# ble_clone.net
KiCad netlist of a schematic drawn in EAGLE
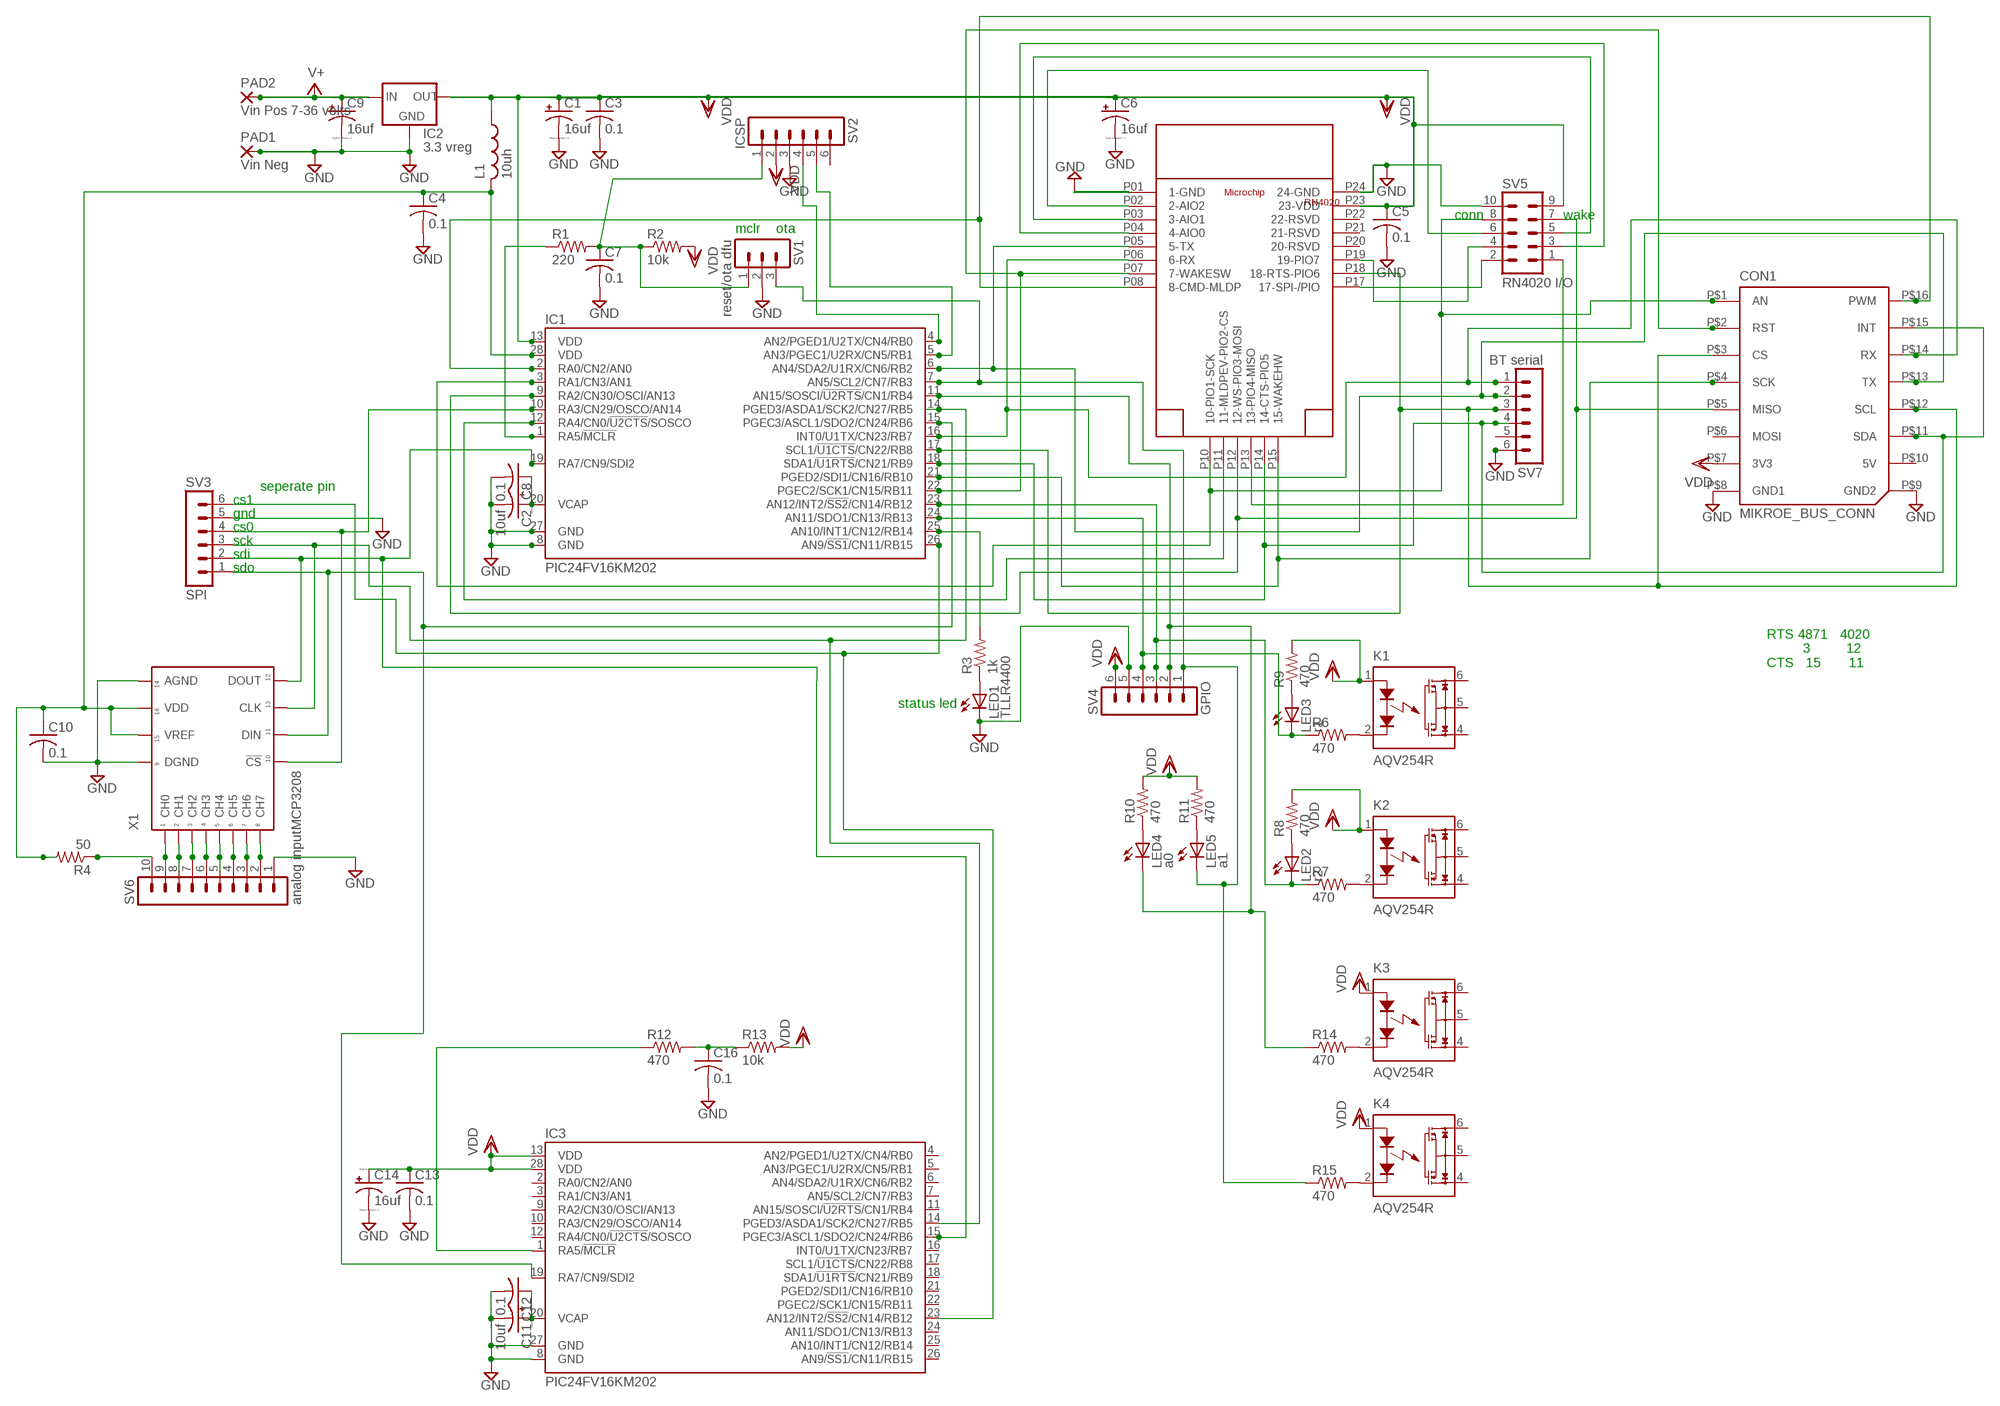
[diagram p0: schematic, sheet 1]

(export (version "E")
  (design (tool "Eeschema 10.0.6"))
  (components
    (comp (ref "C1")
      (value "16uf")
      (footprint "eagle-import:TAP5-45")
      (libsource (lib "eagle-import") (part "CPOL-USTAP5-45"))
    )
    (comp (ref "C2")
      (value "10uf")
      (footprint "eagle-import:TAP5-45")
      (libsource (lib "eagle-import") (part "CPOL-USTAP5-45"))
    )
    (comp (ref "C3")
      (value "0.1")
      (footprint "eagle-import:C025-024X044")
      (libsource (lib "eagle-import") (part "resistor_C-US025-024X044"))
    )
    (comp (ref "C4")
      (value "0.1")
      (footprint "eagle-import:C025-024X044")
      (libsource (lib "eagle-import") (part "resistor_C-US025-024X044"))
    )
    (comp (ref "C5")
      (value "0.1")
      (footprint "eagle-import:C025-024X044")
      (libsource (lib "eagle-import") (part "resistor_C-US025-024X044"))
    )
    (comp (ref "C6")
      (value "16uf")
      (footprint "eagle-import:TAP5-45")
      (libsource (lib "eagle-import") (part "CPOL-USTAP5-45"))
    )
    (comp (ref "C7")
      (value "0.1")
      (footprint "eagle-import:C025-024X044")
      (libsource (lib "eagle-import") (part "resistor_C-US025-024X044"))
    )
    (comp (ref "C8")
      (value "0.1")
      (footprint "eagle-import:C025-024X044")
      (libsource (lib "eagle-import") (part "resistor_C-US025-024X044"))
    )
    (comp (ref "C9")
      (value "16uf")
      (footprint "eagle-import:TAP5-45")
      (libsource (lib "eagle-import") (part "CPOL-USTAP5-45"))
    )
    (comp (ref "C10")
      (value "0.1")
      (footprint "eagle-import:C025-024X044")
      (libsource (lib "eagle-import") (part "resistor_C-US025-024X044"))
    )
    (comp (ref "C11")
      (value "10uf")
      (footprint "eagle-import:TAP5-45")
      (libsource (lib "eagle-import") (part "CPOL-USTAP5-45"))
    )
    (comp (ref "C12")
      (value "0.1")
      (footprint "eagle-import:C0805")
      (libsource (lib "eagle-import") (part "C-USC0805"))
    )
    (comp (ref "C13")
      (value "0.1")
      (footprint "eagle-import:C0805")
      (libsource (lib "eagle-import") (part "C-USC0805"))
    )
    (comp (ref "C14")
      (value "16uf")
      (footprint "eagle-import:TAP5-45")
      (libsource (lib "eagle-import") (part "CPOL-USTAP5-45"))
    )
    (comp (ref "C16")
      (value "0.1")
      (footprint "eagle-import:C0805")
      (libsource (lib "eagle-import") (part "C-USC0805"))
    )
    (comp (ref "CON1")
      (value "MIKROE_BUS_CONN")
      (footprint "eagle-import:MIKROBUS_HOST_CONN")
      (libsource (lib "eagle-import") (part "MIKROE_BUS_CONN"))
    )
    (comp (ref "IC1")
      (value "PIC24FV16KM202")
      (footprint "eagle-import:DIL28-3")
      (libsource (lib "eagle-import") (part "PIC24FVXXKA302-SP"))
    )
    (comp (ref "IC2")
      (value "3.3 vreg")
      (footprint "eagle-import:78XXL")
      (libsource (lib "eagle-import") (part "78XXL"))
    )
    (comp (ref "IC3")
      (value "PIC24FV16KM202")
      (footprint "eagle-import:DIL28-3")
      (libsource (lib "eagle-import") (part "PIC24FVXXKA302-SP"))
    )
    (comp (ref "K1")
      (value "AQV254R")
      (footprint "eagle-import:DIL06")
      (fields (field (name "MF") "AROMAT/ MATSUSHITA") (field (name "MPN") "AQV254"))
      (libsource (lib "eagle-import") (part "AQV254R"))
    )
    (comp (ref "K2")
      (value "AQV254R")
      (footprint "eagle-import:DIL06")
      (fields (field (name "MF") "AROMAT/ MATSUSHITA") (field (name "MPN") "AQV254"))
      (libsource (lib "eagle-import") (part "AQV254R"))
    )
    (comp (ref "K3")
      (value "AQV254R")
      (footprint "eagle-import:DIL06")
      (fields (field (name "MF") "AROMAT/ MATSUSHITA") (field (name "MPN") "AQV254"))
      (libsource (lib "eagle-import") (part "AQV254R"))
    )
    (comp (ref "K4")
      (value "AQV254R")
      (footprint "eagle-import:DIL06")
      (fields (field (name "MF") "AROMAT/ MATSUSHITA") (field (name "MPN") "AQV254"))
      (libsource (lib "eagle-import") (part "AQV254R"))
    )
    (comp (ref "L1")
      (value "10uh")
      (footprint "eagle-import:0204_5")
      (libsource (lib "eagle-import") (part "L-US0204/5"))
    )
    (comp (ref "LED1")
      (value "TLLR4400")
      (footprint "eagle-import:LED3MM")
      (fields (field (name "MF") "VISHAY SEMICONDUCTOR"))
      (libsource (lib "eagle-import") (part "TLLR4400"))
    )
    (comp (ref "LED2")
      (value "r2")
      (footprint "eagle-import:LED3MM")
      (libsource (lib "eagle-import") (part "LED3MM"))
    )
    (comp (ref "LED3")
      (value "r1")
      (footprint "eagle-import:LED3MM")
      (libsource (lib "eagle-import") (part "LED3MM"))
    )
    (comp (ref "LED4")
      (value "a0")
      (footprint "eagle-import:LED3MM")
      (libsource (lib "eagle-import") (part "LED3MM"))
    )
    (comp (ref "LED5")
      (value "a1")
      (footprint "eagle-import:LED3MM")
      (libsource (lib "eagle-import") (part "LED3MM"))
    )
    (comp (ref "PAD1")
      (value "Vin Neg")
      (footprint "eagle-import:2,54_1,0")
      (libsource (lib "eagle-import") (part "2,54/1,0"))
    )
    (comp (ref "PAD2")
      (value "Vin Pos 7-36 volts")
      (footprint "eagle-import:2,54_1,0")
      (libsource (lib "eagle-import") (part "2,54/1,0"))
    )
    (comp (ref "R1")
      (value "220")
      (footprint "eagle-import:0204V")
      (libsource (lib "eagle-import") (part "R-US_0204/2V"))
    )
    (comp (ref "R2")
      (value "10k")
      (footprint "eagle-import:0204V")
      (libsource (lib "eagle-import") (part "R-US_0204/2V"))
    )
    (comp (ref "R3")
      (value "1k")
      (footprint "eagle-import:0204V")
      (libsource (lib "eagle-import") (part "R-US_0204/2V"))
    )
    (comp (ref "R4")
      (value "50")
      (footprint "eagle-import:0204V")
      (libsource (lib "eagle-import") (part "R-US_0204/2V"))
    )
    (comp (ref "R6")
      (value "470")
      (footprint "eagle-import:0204V")
      (libsource (lib "eagle-import") (part "R-US_0204/2V"))
    )
    (comp (ref "R7")
      (value "470")
      (footprint "eagle-import:0204V")
      (libsource (lib "eagle-import") (part "R-US_0204/2V"))
    )
    (comp (ref "R8")
      (value "470")
      (footprint "eagle-import:0204V")
      (libsource (lib "eagle-import") (part "R-US_0204/2V"))
    )
    (comp (ref "R9")
      (value "470")
      (footprint "eagle-import:0204V")
      (libsource (lib "eagle-import") (part "R-US_0204/2V"))
    )
    (comp (ref "R10")
      (value "470")
      (footprint "eagle-import:0204V")
      (libsource (lib "eagle-import") (part "R-US_0204/2V"))
    )
    (comp (ref "R11")
      (value "470")
      (footprint "eagle-import:0204V")
      (libsource (lib "eagle-import") (part "R-US_0204/2V"))
    )
    (comp (ref "R12")
      (value "470")
      (footprint "eagle-import:0204V")
      (libsource (lib "eagle-import") (part "R-US_0204/2V"))
    )
    (comp (ref "R13")
      (value "10k")
      (footprint "eagle-import:0204V")
      (libsource (lib "eagle-import") (part "R-US_0204/2V"))
    )
    (comp (ref "R14")
      (value "470")
      (footprint "eagle-import:0204V")
      (libsource (lib "eagle-import") (part "R-US_0204/2V"))
    )
    (comp (ref "R15")
      (value "470")
      (footprint "eagle-import:0204V")
      (libsource (lib "eagle-import") (part "R-US_0204/2V"))
    )
    (comp (ref "SV1")
      (value "reset/ota dfu")
      (footprint "eagle-import:MA03-1")
      (libsource (lib "eagle-import") (part "MA03-1"))
    )
    (comp (ref "SV2")
      (value "ICSP")
      (footprint "eagle-import:MA06-1")
      (libsource (lib "eagle-import") (part "MA06-1"))
    )
    (comp (ref "SV3")
      (value "SPI")
      (footprint "eagle-import:MA06-1")
      (libsource (lib "eagle-import") (part "MA06-1"))
    )
    (comp (ref "SV4")
      (value "GPIO")
      (footprint "eagle-import:MA06-1")
      (libsource (lib "eagle-import") (part "MA06-1"))
    )
    (comp (ref "SV5")
      (value "RN4020 I/O")
      (footprint "eagle-import:MA05-2")
      (libsource (lib "eagle-import") (part "MA05-2"))
    )
    (comp (ref "SV6")
      (value "analog input")
      (footprint "eagle-import:MA10-1")
      (libsource (lib "eagle-import") (part "MA10-1"))
    )
    (comp (ref "SV7")
      (value "BT serial")
      (footprint "eagle-import:MA06-1")
      (libsource (lib "eagle-import") (part "MA06-1"))
    )
    (comp (ref "U$1")
      (value "RN4020")
      (footprint "eagle-import:RN4020SMD")
      (libsource (lib "eagle-import") (part "RN4020"))
    )
    (comp (ref "X1")
      (value "MCP3208")
      (footprint "eagle-import:DIP16")
      (libsource (lib "eagle-import") (part "21298EDIP"))
    )
  )
  (nets
    (net (code "1") (name "GND") (class "Default")
      (node (ref "C1") (pin "-") (pinfunction "-_-") (pintype "passive"))
      (node (ref "C10") (pin "2") (pinfunction "2_2") (pintype "passive"))
      (node (ref "C11") (pin "-") (pinfunction "-_-") (pintype "passive"))
      (node (ref "C12") (pin "2") (pinfunction "2_2") (pintype "passive"))
      (node (ref "C13") (pin "2") (pinfunction "2_2") (pintype "passive"))
      (node (ref "C14") (pin "-") (pinfunction "-_-") (pintype "passive"))
      (node (ref "C16") (pin "2") (pinfunction "2_2") (pintype "passive"))
      (node (ref "C2") (pin "-") (pinfunction "-_-") (pintype "passive"))
      (node (ref "C3") (pin "2") (pinfunction "2_2") (pintype "passive"))
      (node (ref "C4") (pin "2") (pinfunction "2_2") (pintype "passive"))
      (node (ref "C5") (pin "2") (pinfunction "2_2") (pintype "passive"))
      (node (ref "C6") (pin "-") (pinfunction "-_-") (pintype "passive"))
      (node (ref "C7") (pin "2") (pinfunction "2_2") (pintype "passive"))
      (node (ref "C8") (pin "2") (pinfunction "2_2") (pintype "passive"))
      (node (ref "C9") (pin "-") (pinfunction "-_-") (pintype "passive"))
      (node (ref "CON1") (pin "P$8") (pinfunction "GND1_P$8") (pintype "bidirectional"))
      (node (ref "CON1") (pin "P$9") (pinfunction "GND2_P$9") (pintype "bidirectional"))
      (node (ref "IC1") (pin "27") (pinfunction "GND_27") (pintype "power_in"))
      (node (ref "IC1") (pin "8") (pinfunction "GND_8") (pintype "power_in"))
      (node (ref "IC2") (pin "GND") (pinfunction "GND_GND") (pintype "input"))
      (node (ref "IC3") (pin "27") (pinfunction "GND_27") (pintype "power_in"))
      (node (ref "IC3") (pin "8") (pinfunction "GND_8") (pintype "power_in"))
      (node (ref "LED1") (pin "K") (pinfunction "C_K") (pintype "passive"))
      (node (ref "PAD1") (pin "1") (pinfunction "P_1") (pintype "passive"))
      (node (ref "SV1") (pin "2") (pinfunction "2_2") (pintype "passive"))
      (node (ref "SV2") (pin "3") (pinfunction "3_3") (pintype "passive"))
      (node (ref "SV3") (pin "5") (pinfunction "5_5") (pintype "passive"))
      (node (ref "SV4") (pin "5") (pinfunction "5_5") (pintype "passive"))
      (node (ref "SV5") (pin "10") (pinfunction "10_10") (pintype "passive"))
      (node (ref "SV6") (pin "1") (pinfunction "1_1") (pintype "passive"))
      (node (ref "SV7") (pin "6") (pinfunction "6_6") (pintype "passive"))
      (node (ref "U$1") (pin "P01") (pinfunction "1-GND_P01") (pintype "bidirectional"))
      (node (ref "U$1") (pin "P24") (pinfunction "24-GND_P24") (pintype "bidirectional"))
      (node (ref "X1") (pin "P$14") (pinfunction "AGND_P$14") (pintype "bidirectional"))
      (node (ref "X1") (pin "P$9") (pinfunction "DGND_P$9") (pintype "bidirectional"))
    )
    (net (code "2") (name "Net-(C7-Pad1)") (class "Default")
      (node (ref "C7") (pin "1") (pinfunction "1_1") (pintype "passive"))
      (node (ref "R1") (pin "2") (pinfunction "2_2") (pintype "passive"))
      (node (ref "R2") (pin "1") (pinfunction "1_1") (pintype "passive"))
      (node (ref "SV1") (pin "1") (pinfunction "1_1") (pintype "passive"))
      (node (ref "SV2") (pin "1") (pinfunction "1_1") (pintype "passive"))
    )
    (net (code "3") (name "Net-(C16-Pad1)") (class "Default")
      (node (ref "C16") (pin "1") (pinfunction "1_1") (pintype "passive"))
      (node (ref "R12") (pin "2") (pinfunction "2_2") (pintype "passive"))
      (node (ref "R13") (pin "1") (pinfunction "1_1") (pintype "passive"))
    )
    (net (code "4") (name "Net-(CON1-AN)") (class "Default")
      (node (ref "CON1") (pin "P$1") (pinfunction "AN_P$1") (pintype "bidirectional"))
      (node (ref "IC1") (pin "3") (pinfunction "RA1/CN3/AN1_3") (pintype "bidirectional"))
      (node (ref "SV5") (pin "8") (pinfunction "8_8") (pintype "passive"))
      (node (ref "U$1") (pin "P10") (pinfunction "10-PIO1-SCK_P10") (pintype "bidirectional"))
    )
    (net (code "5") (name "Net-(CON1-CS)") (class "Default")
      (node (ref "CON1") (pin "P$12") (pinfunction "SCL_P$12") (pintype "bidirectional"))
      (node (ref "CON1") (pin "P$3") (pinfunction "CS_P$3") (pintype "bidirectional"))
      (node (ref "IC1") (pin "17") (pinfunction "SCL1/~{U1CTS}/CN22/RB8_17") (pintype "bidirectional"))
      (node (ref "SV7") (pin "3") (pinfunction "3_3") (pintype "passive"))
      (node (ref "U$1") (pin "P18") (pinfunction "18-RTS-PIO6_P18") (pintype "bidirectional"))
    )
    (net (code "6") (name "Net-(CON1-INT)") (class "Default")
      (node (ref "CON1") (pin "P$11") (pinfunction "SDA_P$11") (pintype "bidirectional"))
      (node (ref "CON1") (pin "P$15") (pinfunction "INT_P$15") (pintype "bidirectional"))
      (node (ref "IC1") (pin "18") (pinfunction "SDA1/~{U1RTS}/CN21/RB9_18") (pintype "bidirectional"))
      (node (ref "SV7") (pin "4") (pinfunction "4_4") (pintype "passive"))
      (node (ref "U$1") (pin "P14") (pinfunction "14-CTS-PIO5_P14") (pintype "bidirectional"))
    )
    (net (code "7") (name "Net-(CON1-MISO)") (class "Default")
      (node (ref "CON1") (pin "P$5") (pinfunction "MISO_P$5") (pintype "bidirectional"))
      (node (ref "IC1") (pin "9") (pinfunction "RA2/CN30/OSCI/AN13_9") (pintype "bidirectional"))
      (node (ref "SV5") (pin "7") (pinfunction "7_7") (pintype "passive"))
      (node (ref "U$1") (pin "P12") (pinfunction "12-WS-PIO3-MOSI_P12") (pintype "bidirectional"))
    )
    (net (code "8") (name "Net-(CON1-PWM)") (class "Default")
      (node (ref "CON1") (pin "P$16") (pinfunction "PWM_P$16") (pintype "bidirectional"))
      (node (ref "IC1") (pin "2") (pinfunction "RA0/CN2/AN0_2") (pintype "bidirectional"))
      (node (ref "U$1") (pin "P08") (pinfunction "8-CMD-MLDP_P08") (pintype "bidirectional"))
    )
    (net (code "9") (name "Net-(CON1-RST)") (class "Default")
      (node (ref "CON1") (pin "P$2") (pinfunction "RST_P$2") (pintype "bidirectional"))
      (node (ref "IC1") (pin "22") (pinfunction "PGEC2/SCK1/CN15/RB11_22") (pintype "bidirectional"))
      (node (ref "U$1") (pin "P07") (pinfunction "7-WAKESW_P07") (pintype "bidirectional"))
    )
    (net (code "10") (name "Net-(CON1-RX)") (class "Default")
      (node (ref "CON1") (pin "P$14") (pinfunction "RX_P$14") (pintype "bidirectional"))
      (node (ref "IC1") (pin "16") (pinfunction "INT0/U1TX/CN23/RB7_16") (pintype "bidirectional"))
      (node (ref "SV7") (pin "1") (pinfunction "1_1") (pintype "passive"))
      (node (ref "U$1") (pin "P06") (pinfunction "6-RX_P06") (pintype "bidirectional"))
    )
    (net (code "11") (name "Net-(CON1-SCK)") (class "Default")
      (node (ref "CON1") (pin "P$4") (pinfunction "SCK_P$4") (pintype "bidirectional"))
      (node (ref "IC1") (pin "21") (pinfunction "PGED2/SDI1/CN16/RB10_21") (pintype "bidirectional"))
      (node (ref "U$1") (pin "P15") (pinfunction "15-WAKEHW_P15") (pintype "bidirectional"))
    )
    (net (code "12") (name "Net-(CON1-TX)") (class "Default")
      (node (ref "CON1") (pin "P$13") (pinfunction "TX_P$13") (pintype "bidirectional"))
      (node (ref "IC1") (pin "6") (pinfunction "AN4/SDA2/U1RX/CN6/RB2_6") (pintype "bidirectional"))
      (node (ref "SV7") (pin "2") (pinfunction "2_2") (pintype "passive"))
      (node (ref "U$1") (pin "P05") (pinfunction "5-TX_P05") (pintype "bidirectional"))
    )
    (net (code "13") (name "Net-(IC1-AN2{slash}PGED1{slash}U2TX{slash}CN4{slash}RB0)") (class "Default")
      (node (ref "IC1") (pin "4") (pinfunction "AN2/PGED1/U2TX/CN4/RB0_4") (pintype "bidirectional"))
      (node (ref "SV2") (pin "4") (pinfunction "4_4") (pintype "passive"))
    )
    (net (code "14") (name "Net-(IC1-AN3{slash}PGEC1{slash}U2RX{slash}CN5{slash}RB1)") (class "Default")
      (node (ref "IC1") (pin "5") (pinfunction "AN3/PGEC1/U2RX/CN5/RB1_5") (pintype "bidirectional"))
      (node (ref "SV2") (pin "5") (pinfunction "5_5") (pintype "passive"))
    )
    (net (code "15") (name "Net-(IC1-AN5{slash}SCL2{slash}CN7{slash}RB3)") (class "Default")
      (node (ref "IC1") (pin "7") (pinfunction "AN5/SCL2/CN7/RB3_7") (pintype "bidirectional"))
      (node (ref "LED5") (pin "K") (pinfunction "C_K") (pintype "passive"))
      (node (ref "R15") (pin "1") (pinfunction "1_1") (pintype "passive"))
      (node (ref "SV1") (pin "3") (pinfunction "3_3") (pintype "passive"))
      (node (ref "SV4") (pin "1") (pinfunction "1_1") (pintype "passive"))
    )
    (net (code "16") (name "Net-(IC1-AN9{slash}~{SS1}{slash}CN11{slash}RB15)") (class "Default")
      (node (ref "IC1") (pin "26") (pinfunction "AN9/~{SS1}/CN11/RB15_26") (pintype "bidirectional"))
      (node (ref "IC3") (pin "23") (pinfunction "AN12/INT2/~{SS2}/CN14/RB12_23") (pintype "bidirectional"))
      (node (ref "SV3") (pin "6") (pinfunction "6_6") (pintype "passive"))
    )
    (net (code "17") (name "Net-(IC1-AN10{slash}INT1{slash}CN12{slash}RB14)") (class "Default")
      (node (ref "IC1") (pin "25") (pinfunction "AN10/INT1/CN12/RB14_25") (pintype "bidirectional"))
      (node (ref "R3") (pin "2") (pinfunction "2_2") (pintype "passive"))
    )
    (net (code "18") (name "Net-(IC1-AN11{slash}SDO1{slash}CN13{slash}RB13)") (class "Default")
      (node (ref "IC1") (pin "24") (pinfunction "AN11/SDO1/CN13/RB13_24") (pintype "bidirectional"))
      (node (ref "LED3") (pin "K") (pinfunction "C_K") (pintype "passive"))
      (node (ref "R6") (pin "1") (pinfunction "1_1") (pintype "passive"))
      (node (ref "SV4") (pin "4") (pinfunction "4_4") (pintype "passive"))
    )
    (net (code "19") (name "Net-(IC1-AN12{slash}INT2{slash}~{SS2}{slash}CN14{slash}RB12)") (class "Default")
      (node (ref "IC1") (pin "23") (pinfunction "AN12/INT2/~{SS2}/CN14/RB12_23") (pintype "bidirectional"))
      (node (ref "LED2") (pin "K") (pinfunction "C_K") (pintype "passive"))
      (node (ref "R7") (pin "1") (pinfunction "1_1") (pintype "passive"))
      (node (ref "SV4") (pin "3") (pinfunction "3_3") (pintype "passive"))
    )
    (net (code "20") (name "Net-(IC1-AN15{slash}SOSCI{slash}~{U2RTS}{slash}CN1{slash}RB4)") (class "Default")
      (node (ref "IC1") (pin "11") (pinfunction "AN15/SOSCI/~{U2RTS}/CN1/RB4_11") (pintype "bidirectional"))
      (node (ref "LED4") (pin "K") (pinfunction "C_K") (pintype "passive"))
      (node (ref "R14") (pin "1") (pinfunction "1_1") (pintype "passive"))
      (node (ref "SV4") (pin "2") (pinfunction "2_2") (pintype "passive"))
    )
    (net (code "21") (name "Net-(IC1-PGEC3{slash}ASCL1{slash}SDO2{slash}CN24{slash}RB6)") (class "Default")
      (node (ref "IC1") (pin "15") (pinfunction "PGEC3/ASCL1/SDO2/CN24/RB6_15") (pintype "bidirectional"))
      (node (ref "IC3") (pin "19") (pinfunction "RA7/CN9/SDI2_19") (pintype "bidirectional"))
      (node (ref "SV3") (pin "1") (pinfunction "1_1") (pintype "passive"))
      (node (ref "X1") (pin "P$11") (pinfunction "DIN_P$11") (pintype "bidirectional"))
    )
    (net (code "22") (name "Net-(IC1-PGED3{slash}ASDA1{slash}SCK2{slash}CN27{slash}RB5)") (class "Default")
      (node (ref "IC1") (pin "14") (pinfunction "PGED3/ASDA1/SCK2/CN27/RB5_14") (pintype "bidirectional"))
      (node (ref "IC3") (pin "14") (pinfunction "PGED3/ASDA1/SCK2/CN27/RB5_14") (pintype "bidirectional"))
      (node (ref "SV3") (pin "3") (pinfunction "3_3") (pintype "passive"))
      (node (ref "X1") (pin "P$13") (pinfunction "CLK_P$13") (pintype "bidirectional"))
    )
    (net (code "23") (name "Net-(IC1-RA3{slash}CN29{slash}OSCO{slash}AN14)") (class "Default")
      (node (ref "IC1") (pin "10") (pinfunction "RA3/CN29/OSCO/AN14_10") (pintype "bidirectional"))
      (node (ref "SV3") (pin "4") (pinfunction "4_4") (pintype "passive"))
      (node (ref "X1") (pin "P$10") (pinfunction "~{CS}_P$10") (pintype "bidirectional"))
    )
    (net (code "24") (name "Net-(IC1-RA4{slash}CN0{slash}~{U2CTS}{slash}SOSCO)") (class "Default")
      (node (ref "IC1") (pin "12") (pinfunction "RA4/CN0/~{U2CTS}/SOSCO_12") (pintype "bidirectional"))
      (node (ref "U$1") (pin "P11") (pinfunction "11-MLDPEV-PIO2-CS_P11") (pintype "bidirectional"))
    )
    (net (code "25") (name "Net-(IC1-RA5{slash}~{MCLR})") (class "Default")
      (node (ref "IC1") (pin "1") (pinfunction "RA5/~{MCLR}_1") (pintype "bidirectional"))
      (node (ref "R1") (pin "1") (pinfunction "1_1") (pintype "passive"))
    )
    (net (code "26") (name "Net-(IC1-RA7{slash}CN9{slash}SDI2)") (class "Default")
      (node (ref "IC1") (pin "19") (pinfunction "RA7/CN9/SDI2_19") (pintype "bidirectional"))
      (node (ref "IC3") (pin "15") (pinfunction "PGEC3/ASCL1/SDO2/CN24/RB6_15") (pintype "bidirectional"))
      (node (ref "SV3") (pin "2") (pinfunction "2_2") (pintype "passive"))
      (node (ref "X1") (pin "P$12") (pinfunction "DOUT_P$12") (pintype "bidirectional"))
    )
    (net (code "27") (name "Net-(IC1-VCAP)") (class "Default")
      (node (ref "C2") (pin "+") (pinfunction "+_+") (pintype "passive"))
      (node (ref "C8") (pin "1") (pinfunction "1_1") (pintype "passive"))
      (node (ref "IC1") (pin "20") (pinfunction "VCAP_20") (pintype "passive"))
    )
    (net (code "28") (name "Net-(IC3-RA5{slash}~{MCLR})") (class "Default")
      (node (ref "IC3") (pin "1") (pinfunction "RA5/~{MCLR}_1") (pintype "bidirectional"))
      (node (ref "R12") (pin "1") (pinfunction "1_1") (pintype "passive"))
    )
    (net (code "29") (name "Net-(IC3-VCAP)") (class "Default")
      (node (ref "C11") (pin "+") (pinfunction "+_+") (pintype "passive"))
      (node (ref "C12") (pin "1") (pinfunction "1_1") (pintype "passive"))
      (node (ref "IC3") (pin "20") (pinfunction "VCAP_20") (pintype "passive"))
    )
    (net (code "30") (name "Net-(K1-K)") (class "Default")
      (node (ref "K1") (pin "2") (pinfunction "K_2") (pintype "passive"))
      (node (ref "R6") (pin "2") (pinfunction "2_2") (pintype "passive"))
    )
    (net (code "31") (name "Net-(K2-K)") (class "Default")
      (node (ref "K2") (pin "2") (pinfunction "K_2") (pintype "passive"))
      (node (ref "R7") (pin "2") (pinfunction "2_2") (pintype "passive"))
    )
    (net (code "32") (name "Net-(K3-K)") (class "Default")
      (node (ref "K3") (pin "2") (pinfunction "K_2") (pintype "passive"))
      (node (ref "R14") (pin "2") (pinfunction "2_2") (pintype "passive"))
    )
    (net (code "33") (name "Net-(K4-K)") (class "Default")
      (node (ref "K4") (pin "2") (pinfunction "K_2") (pintype "passive"))
      (node (ref "R15") (pin "2") (pinfunction "2_2") (pintype "passive"))
    )
    (net (code "34") (name "Net-(LED1-PadA)") (class "Default")
      (node (ref "LED1") (pin "A") (pinfunction "A_A") (pintype "passive"))
      (node (ref "R3") (pin "1") (pinfunction "1_1") (pintype "passive"))
    )
    (net (code "35") (name "Net-(LED2-PadA)") (class "Default")
      (node (ref "LED2") (pin "A") (pinfunction "A_A") (pintype "passive"))
      (node (ref "R8") (pin "1") (pinfunction "1_1") (pintype "passive"))
    )
    (net (code "36") (name "Net-(LED3-PadA)") (class "Default")
      (node (ref "LED3") (pin "A") (pinfunction "A_A") (pintype "passive"))
      (node (ref "R9") (pin "1") (pinfunction "1_1") (pintype "passive"))
    )
    (net (code "37") (name "Net-(LED4-PadA)") (class "Default")
      (node (ref "LED4") (pin "A") (pinfunction "A_A") (pintype "passive"))
      (node (ref "R10") (pin "1") (pinfunction "1_1") (pintype "passive"))
    )
    (net (code "38") (name "Net-(LED5-PadA)") (class "Default")
      (node (ref "LED5") (pin "A") (pinfunction "A_A") (pintype "passive"))
      (node (ref "R11") (pin "1") (pinfunction "1_1") (pintype "passive"))
    )
    (net (code "39") (name "Net-(R4-Pad1)") (class "Default")
      (node (ref "R4") (pin "1") (pinfunction "1_1") (pintype "passive"))
      (node (ref "SV6") (pin "10") (pinfunction "10_10") (pintype "passive"))
    )
    (net (code "40") (name "Net-(U$1-2-AIO2)") (class "Default")
      (node (ref "SV5") (pin "6") (pinfunction "6_6") (pintype "passive"))
      (node (ref "U$1") (pin "P02") (pinfunction "2-AIO2_P02") (pintype "bidirectional"))
    )
    (net (code "41") (name "Net-(U$1-3-AIO1)") (class "Default")
      (node (ref "SV5") (pin "5") (pinfunction "5_5") (pintype "passive"))
      (node (ref "U$1") (pin "P03") (pinfunction "3-AIO1_P03") (pintype "bidirectional"))
    )
    (net (code "42") (name "Net-(U$1-4-AIO0)") (class "Default")
      (node (ref "SV5") (pin "3") (pinfunction "3_3") (pintype "passive"))
      (node (ref "U$1") (pin "P04") (pinfunction "4-AIO0_P04") (pintype "bidirectional"))
    )
    (net (code "43") (name "Net-(U$1-13-PIO4-MISO)") (class "Default")
      (node (ref "SV5") (pin "1") (pinfunction "1_1") (pintype "passive"))
      (node (ref "U$1") (pin "P13") (pinfunction "13-PIO4-MISO_P13") (pintype "bidirectional"))
    )
    (net (code "44") (name "Net-(U$1-17-SPI-{slash}PIO)") (class "Default")
      (node (ref "SV5") (pin "2") (pinfunction "2_2") (pintype "passive"))
      (node (ref "U$1") (pin "P17") (pinfunction "17-SPI-/PIO_P17") (pintype "bidirectional"))
    )
    (net (code "45") (name "Net-(U$1-19-PIO7)") (class "Default")
      (node (ref "SV5") (pin "4") (pinfunction "4_4") (pintype "passive"))
      (node (ref "U$1") (pin "P19") (pinfunction "19-PIO7_P19") (pintype "bidirectional"))
    )
    (net (code "46") (name "Net-(X1-CH0)") (class "Default")
      (node (ref "SV6") (pin "9") (pinfunction "9_9") (pintype "passive"))
      (node (ref "X1") (pin "P$1") (pinfunction "CH0_P$1") (pintype "bidirectional"))
    )
    (net (code "47") (name "Net-(X1-CH1)") (class "Default")
      (node (ref "SV6") (pin "8") (pinfunction "8_8") (pintype "passive"))
      (node (ref "X1") (pin "P$2") (pinfunction "CH1_P$2") (pintype "bidirectional"))
    )
    (net (code "48") (name "Net-(X1-CH2)") (class "Default")
      (node (ref "SV6") (pin "7") (pinfunction "7_7") (pintype "passive"))
      (node (ref "X1") (pin "P$3") (pinfunction "CH2_P$3") (pintype "bidirectional"))
    )
    (net (code "49") (name "Net-(X1-CH3)") (class "Default")
      (node (ref "SV6") (pin "6") (pinfunction "6_6") (pintype "passive"))
      (node (ref "X1") (pin "P$4") (pinfunction "CH3_P$4") (pintype "bidirectional"))
    )
    (net (code "50") (name "Net-(X1-CH4)") (class "Default")
      (node (ref "SV6") (pin "5") (pinfunction "5_5") (pintype "passive"))
      (node (ref "X1") (pin "P$5") (pinfunction "CH4_P$5") (pintype "bidirectional"))
    )
    (net (code "51") (name "Net-(X1-CH5)") (class "Default")
      (node (ref "SV6") (pin "4") (pinfunction "4_4") (pintype "passive"))
      (node (ref "X1") (pin "P$6") (pinfunction "CH5_P$6") (pintype "bidirectional"))
    )
    (net (code "52") (name "Net-(X1-CH6)") (class "Default")
      (node (ref "SV6") (pin "3") (pinfunction "3_3") (pintype "passive"))
      (node (ref "X1") (pin "P$7") (pinfunction "CH6_P$7") (pintype "bidirectional"))
    )
    (net (code "53") (name "Net-(X1-CH7)") (class "Default")
      (node (ref "SV6") (pin "2") (pinfunction "2_2") (pintype "passive"))
      (node (ref "X1") (pin "P$8") (pinfunction "CH7_P$8") (pintype "bidirectional"))
    )
    (net (code "54") (name "Net-(X1-VDD)") (class "Default")
      (node (ref "C10") (pin "1") (pinfunction "1_1") (pintype "passive"))
      (node (ref "C4") (pin "1") (pinfunction "1_1") (pintype "passive"))
      (node (ref "IC1") (pin "28") (pinfunction "VDD_28") (pintype "power_in"))
      (node (ref "L1") (pin "2") (pinfunction "2_2") (pintype "passive"))
      (node (ref "R4") (pin "2") (pinfunction "2_2") (pintype "passive"))
      (node (ref "X1") (pin "P$15") (pinfunction "VREF_P$15") (pintype "bidirectional"))
      (node (ref "X1") (pin "P$16") (pinfunction "VDD_P$16") (pintype "bidirectional"))
    )
    (net (code "55") (name "V+") (class "Default")
      (node (ref "C9") (pin "+") (pinfunction "+_+") (pintype "passive"))
      (node (ref "IC2") (pin "IN") (pinfunction "IN_IN") (pintype "input"))
      (node (ref "PAD2") (pin "1") (pinfunction "P_1") (pintype "passive"))
    )
    (net (code "56") (name "VDD") (class "Default")
      (node (ref "C1") (pin "+") (pinfunction "+_+") (pintype "passive"))
      (node (ref "C13") (pin "1") (pinfunction "1_1") (pintype "passive"))
      (node (ref "C14") (pin "+") (pinfunction "+_+") (pintype "passive"))
      (node (ref "C3") (pin "1") (pinfunction "1_1") (pintype "passive"))
      (node (ref "C5") (pin "1") (pinfunction "1_1") (pintype "passive"))
      (node (ref "C6") (pin "+") (pinfunction "+_+") (pintype "passive"))
      (node (ref "CON1") (pin "P$7") (pinfunction "3V3_P$7") (pintype "bidirectional"))
      (node (ref "IC1") (pin "13") (pinfunction "VDD_13") (pintype "power_in"))
      (node (ref "IC2") (pin "OUT") (pinfunction "OUT_OUT") (pintype "passive"))
      (node (ref "IC3") (pin "13") (pinfunction "VDD_13") (pintype "power_in"))
      (node (ref "IC3") (pin "28") (pinfunction "VDD_28") (pintype "power_in"))
      (node (ref "K1") (pin "1") (pinfunction "A_1") (pintype "passive"))
      (node (ref "K2") (pin "1") (pinfunction "A_1") (pintype "passive"))
      (node (ref "K3") (pin "1") (pinfunction "A_1") (pintype "passive"))
      (node (ref "K4") (pin "1") (pinfunction "A_1") (pintype "passive"))
      (node (ref "L1") (pin "1") (pinfunction "1_1") (pintype "passive"))
      (node (ref "R10") (pin "2") (pinfunction "2_2") (pintype "passive"))
      (node (ref "R11") (pin "2") (pinfunction "2_2") (pintype "passive"))
      (node (ref "R13") (pin "2") (pinfunction "2_2") (pintype "passive"))
      (node (ref "R2") (pin "2") (pinfunction "2_2") (pintype "passive"))
      (node (ref "R8") (pin "2") (pinfunction "2_2") (pintype "passive"))
      (node (ref "R9") (pin "2") (pinfunction "2_2") (pintype "passive"))
      (node (ref "SV2") (pin "2") (pinfunction "2_2") (pintype "passive"))
      (node (ref "SV4") (pin "6") (pinfunction "6_6") (pintype "passive"))
      (node (ref "SV5") (pin "9") (pinfunction "9_9") (pintype "passive"))
      (node (ref "U$1") (pin "P23") (pinfunction "23-VDD_P23") (pintype "bidirectional"))
    )
    (net (code "57") (name "unconnected-(CON1-5V-PadP$10)") (class "Default")
      (node (ref "CON1") (pin "P$10") (pinfunction "5V_P$10") (pintype "bidirectional"))
    )
    (net (code "58") (name "unconnected-(CON1-MOSI-PadP$6)") (class "Default")
      (node (ref "CON1") (pin "P$6") (pinfunction "MOSI_P$6") (pintype "bidirectional"))
    )
    (net (code "59") (name "unconnected-(IC3-AN2{slash}PGED1{slash}U2TX{slash}CN4{slash}RB0-Pad4)") (class "Default")
      (node (ref "IC3") (pin "4") (pinfunction "AN2/PGED1/U2TX/CN4/RB0_4") (pintype "bidirectional"))
    )
    (net (code "60") (name "unconnected-(IC3-AN3{slash}PGEC1{slash}U2RX{slash}CN5{slash}RB1-Pad5)") (class "Default")
      (node (ref "IC3") (pin "5") (pinfunction "AN3/PGEC1/U2RX/CN5/RB1_5") (pintype "bidirectional"))
    )
    (net (code "61") (name "unconnected-(IC3-AN4{slash}SDA2{slash}U1RX{slash}CN6{slash}RB2-Pad6)") (class "Default")
      (node (ref "IC3") (pin "6") (pinfunction "AN4/SDA2/U1RX/CN6/RB2_6") (pintype "bidirectional"))
    )
    (net (code "62") (name "unconnected-(IC3-AN5{slash}SCL2{slash}CN7{slash}RB3-Pad7)") (class "Default")
      (node (ref "IC3") (pin "7") (pinfunction "AN5/SCL2/CN7/RB3_7") (pintype "bidirectional"))
    )
    (net (code "63") (name "unconnected-(IC3-AN9{slash}~{SS1}{slash}CN11{slash}RB15-Pad26)") (class "Default")
      (node (ref "IC3") (pin "26") (pinfunction "AN9/~{SS1}/CN11/RB15_26") (pintype "bidirectional"))
    )
    (net (code "64") (name "unconnected-(IC3-AN10{slash}INT1{slash}CN12{slash}RB14-Pad25)") (class "Default")
      (node (ref "IC3") (pin "25") (pinfunction "AN10/INT1/CN12/RB14_25") (pintype "bidirectional"))
    )
    (net (code "65") (name "unconnected-(IC3-AN11{slash}SDO1{slash}CN13{slash}RB13-Pad24)") (class "Default")
      (node (ref "IC3") (pin "24") (pinfunction "AN11/SDO1/CN13/RB13_24") (pintype "bidirectional"))
    )
    (net (code "66") (name "unconnected-(IC3-AN15{slash}SOSCI{slash}~{U2RTS}{slash}CN1{slash}RB4-Pad11)") (class "Default")
      (node (ref "IC3") (pin "11") (pinfunction "AN15/SOSCI/~{U2RTS}/CN1/RB4_11") (pintype "bidirectional"))
    )
    (net (code "67") (name "unconnected-(IC3-INT0{slash}U1TX{slash}CN23{slash}RB7-Pad16)") (class "Default")
      (node (ref "IC3") (pin "16") (pinfunction "INT0/U1TX/CN23/RB7_16") (pintype "bidirectional"))
    )
    (net (code "68") (name "unconnected-(IC3-PGEC2{slash}SCK1{slash}CN15{slash}RB11-Pad22)") (class "Default")
      (node (ref "IC3") (pin "22") (pinfunction "PGEC2/SCK1/CN15/RB11_22") (pintype "bidirectional"))
    )
    (net (code "69") (name "unconnected-(IC3-PGED2{slash}SDI1{slash}CN16{slash}RB10-Pad21)") (class "Default")
      (node (ref "IC3") (pin "21") (pinfunction "PGED2/SDI1/CN16/RB10_21") (pintype "bidirectional"))
    )
    (net (code "70") (name "unconnected-(IC3-RA0{slash}CN2{slash}AN0-Pad2)") (class "Default")
      (node (ref "IC3") (pin "2") (pinfunction "RA0/CN2/AN0_2") (pintype "bidirectional"))
    )
    (net (code "71") (name "unconnected-(IC3-RA1{slash}CN3{slash}AN1-Pad3)") (class "Default")
      (node (ref "IC3") (pin "3") (pinfunction "RA1/CN3/AN1_3") (pintype "bidirectional"))
    )
    (net (code "72") (name "unconnected-(IC3-RA2{slash}CN30{slash}OSCI{slash}AN13-Pad9)") (class "Default")
      (node (ref "IC3") (pin "9") (pinfunction "RA2/CN30/OSCI/AN13_9") (pintype "bidirectional"))
    )
    (net (code "73") (name "unconnected-(IC3-RA3{slash}CN29{slash}OSCO{slash}AN14-Pad10)") (class "Default")
      (node (ref "IC3") (pin "10") (pinfunction "RA3/CN29/OSCO/AN14_10") (pintype "bidirectional"))
    )
    (net (code "74") (name "unconnected-(IC3-RA4{slash}CN0{slash}~{U2CTS}{slash}SOSCO-Pad12)") (class "Default")
      (node (ref "IC3") (pin "12") (pinfunction "RA4/CN0/~{U2CTS}/SOSCO_12") (pintype "bidirectional"))
    )
    (net (code "75") (name "unconnected-(IC3-SCL1{slash}~{U1CTS}{slash}CN22{slash}RB8-Pad17)") (class "Default")
      (node (ref "IC3") (pin "17") (pinfunction "SCL1/~{U1CTS}/CN22/RB8_17") (pintype "bidirectional"))
    )
    (net (code "76") (name "unconnected-(IC3-SDA1{slash}~{U1RTS}{slash}CN21{slash}RB9-Pad18)") (class "Default")
      (node (ref "IC3") (pin "18") (pinfunction "SDA1/~{U1RTS}/CN21/RB9_18") (pintype "bidirectional"))
    )
    (net (code "77") (name "unconnected-(K1-D1-Pad6)") (class "Default")
      (node (ref "K1") (pin "6") (pinfunction "D1_6") (pintype "passive"))
    )
    (net (code "78") (name "unconnected-(K1-D2-Pad4)") (class "Default")
      (node (ref "K1") (pin "4") (pinfunction "D2_4") (pintype "passive"))
    )
    (net (code "79") (name "unconnected-(K1-S-Pad5)") (class "Default")
      (node (ref "K1") (pin "5") (pinfunction "S_5") (pintype "passive"))
    )
    (net (code "80") (name "unconnected-(K2-D1-Pad6)") (class "Default")
      (node (ref "K2") (pin "6") (pinfunction "D1_6") (pintype "passive"))
    )
    (net (code "81") (name "unconnected-(K2-D2-Pad4)") (class "Default")
      (node (ref "K2") (pin "4") (pinfunction "D2_4") (pintype "passive"))
    )
    (net (code "82") (name "unconnected-(K2-S-Pad5)") (class "Default")
      (node (ref "K2") (pin "5") (pinfunction "S_5") (pintype "passive"))
    )
    (net (code "83") (name "unconnected-(K3-D1-Pad6)") (class "Default")
      (node (ref "K3") (pin "6") (pinfunction "D1_6") (pintype "passive"))
    )
    (net (code "84") (name "unconnected-(K3-D2-Pad4)") (class "Default")
      (node (ref "K3") (pin "4") (pinfunction "D2_4") (pintype "passive"))
    )
    (net (code "85") (name "unconnected-(K3-S-Pad5)") (class "Default")
      (node (ref "K3") (pin "5") (pinfunction "S_5") (pintype "passive"))
    )
    (net (code "86") (name "unconnected-(K4-D1-Pad6)") (class "Default")
      (node (ref "K4") (pin "6") (pinfunction "D1_6") (pintype "passive"))
    )
    (net (code "87") (name "unconnected-(K4-D2-Pad4)") (class "Default")
      (node (ref "K4") (pin "4") (pinfunction "D2_4") (pintype "passive"))
    )
    (net (code "88") (name "unconnected-(K4-S-Pad5)") (class "Default")
      (node (ref "K4") (pin "5") (pinfunction "S_5") (pintype "passive"))
    )
    (net (code "89") (name "unconnected-(SV2-Pad6)") (class "Default")
      (node (ref "SV2") (pin "6") (pinfunction "6_6") (pintype "passive"))
    )
    (net (code "90") (name "unconnected-(SV7-Pad5)") (class "Default")
      (node (ref "SV7") (pin "5") (pinfunction "5_5") (pintype "passive"))
    )
    (net (code "91") (name "unconnected-(U$1-20-RSVD-PadP20)") (class "Default")
      (node (ref "U$1") (pin "P20") (pinfunction "20-RSVD_P20") (pintype "bidirectional"))
    )
    (net (code "92") (name "unconnected-(U$1-21-RSVD-PadP21)") (class "Default")
      (node (ref "U$1") (pin "P21") (pinfunction "21-RSVD_P21") (pintype "bidirectional"))
    )
    (net (code "93") (name "unconnected-(U$1-22-RSVD-PadP22)") (class "Default")
      (node (ref "U$1") (pin "P22") (pinfunction "22-RSVD_P22") (pintype "bidirectional"))
    )
  )
)
